# PIC_16F877A_Board.net
KiCad netlist of a schematic drawn in EAGLE
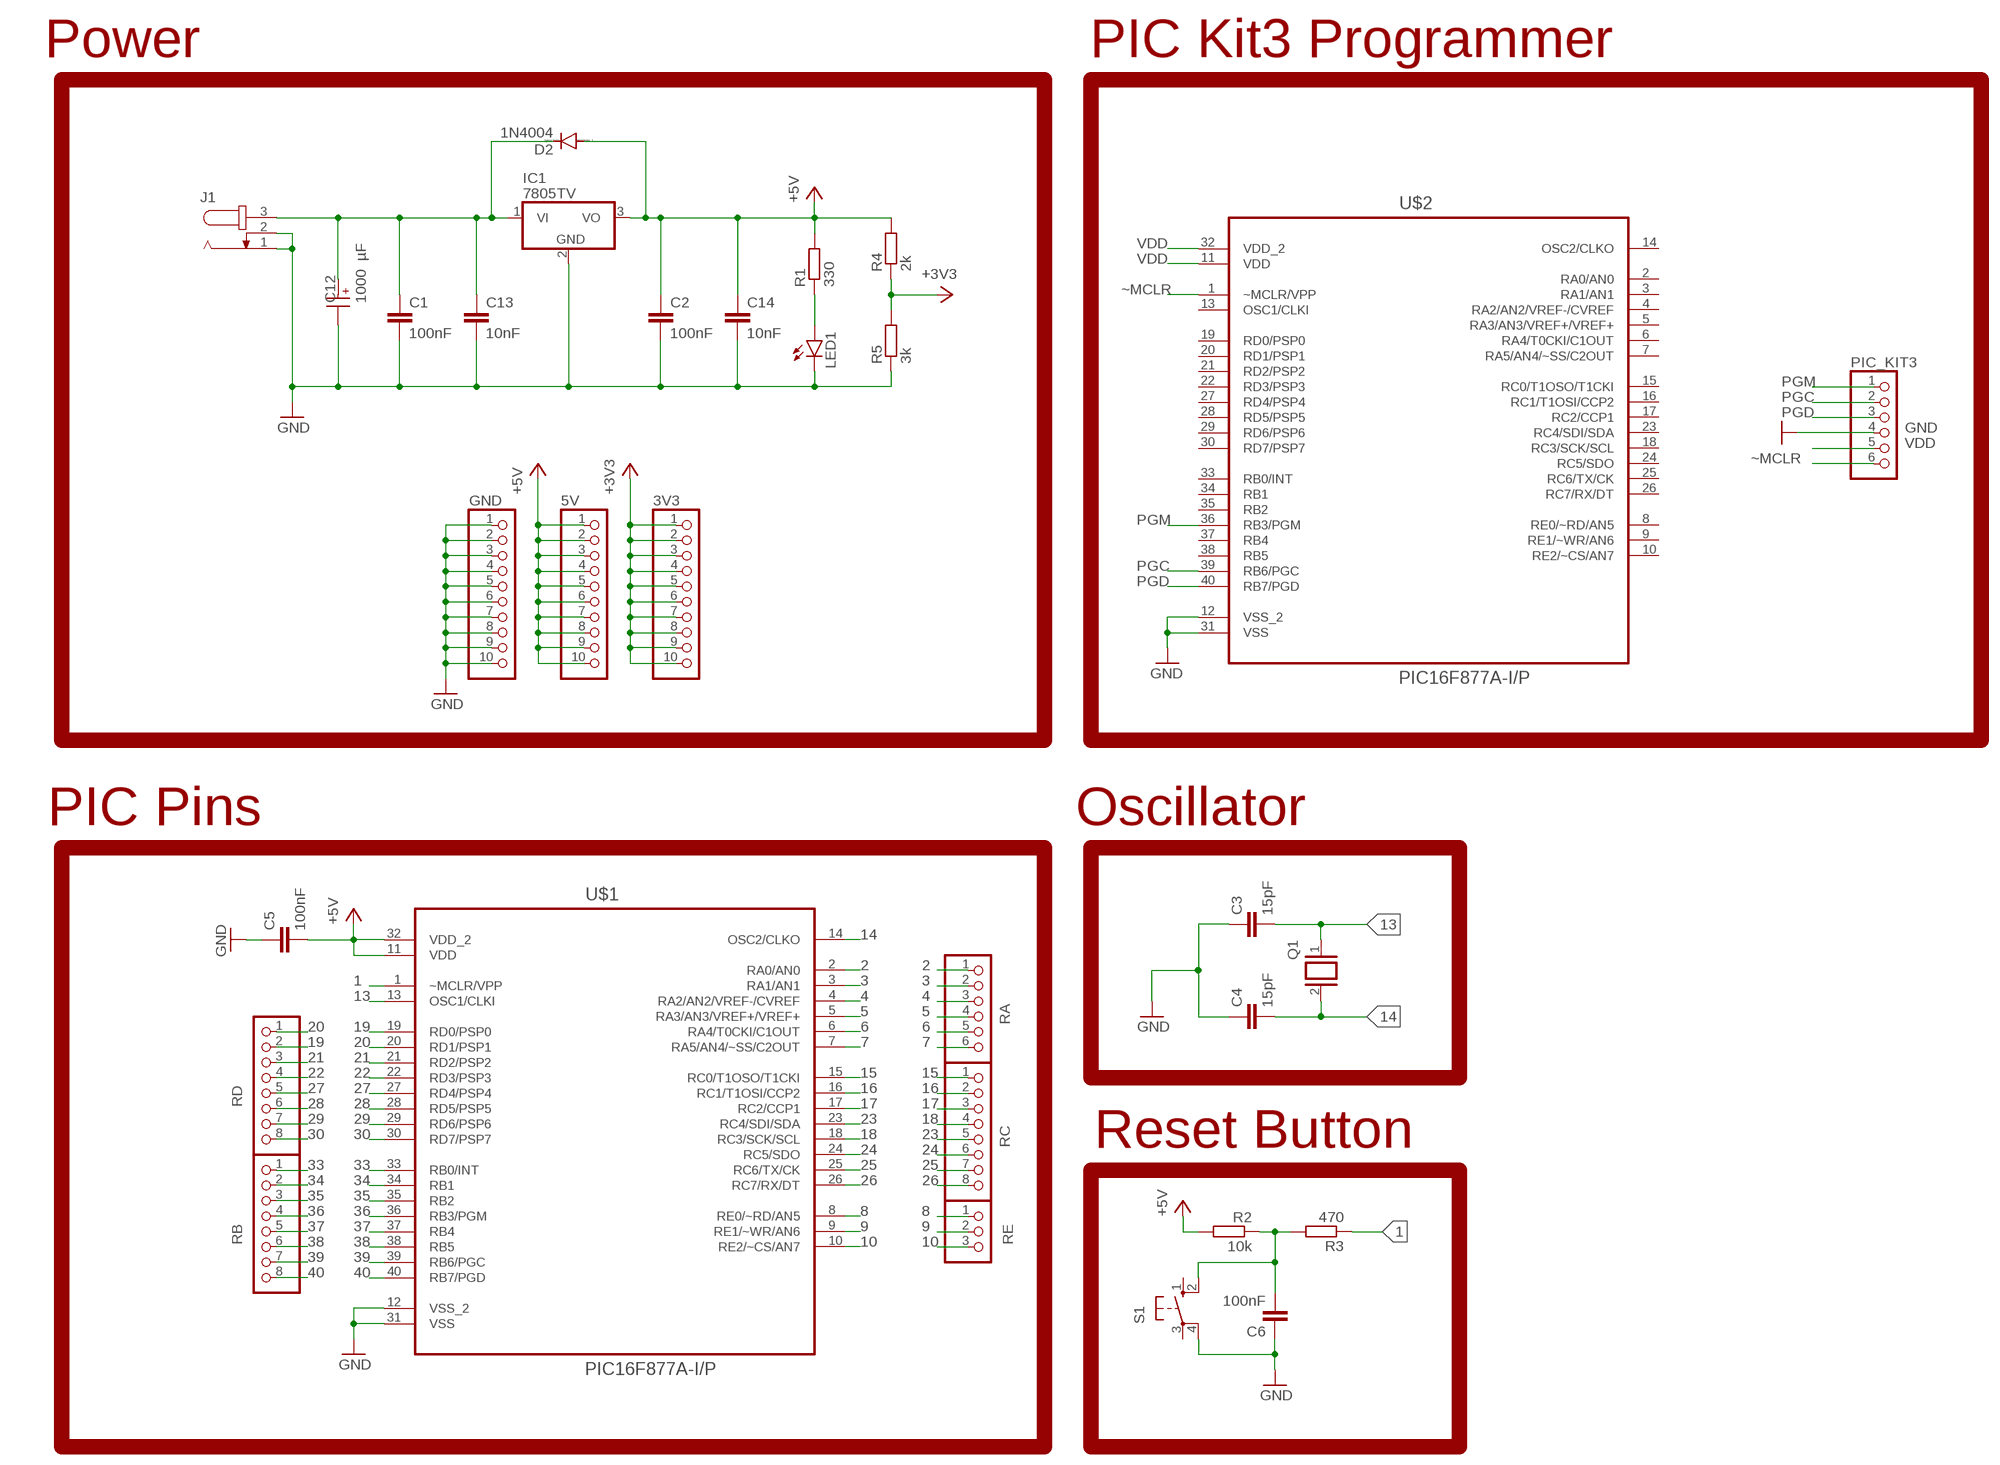
[diagram p0: schematic, sheet 1]

(export (version "E")
  (design (tool "Eeschema 10.0.6"))
  (components
    (comp (ref "3V3")
      (value "PINHD-1X10")
      (footprint "eagle-import:1X10")
      (libsource (lib "eagle-import") (part "PINHD-1X10"))
    )
    (comp (ref "5V")
      (value "PINHD-1X10")
      (footprint "eagle-import:1X10")
      (libsource (lib "eagle-import") (part "PINHD-1X10"))
    )
    (comp (ref "C1")
      (value "100nF")
      (footprint "eagle-import:C025-025X050")
      (libsource (lib "eagle-import") (part "C-EU025-025X050"))
    )
    (comp (ref "C2")
      (value "100nF")
      (footprint "eagle-import:C025-025X050")
      (libsource (lib "eagle-import") (part "C-EU025-025X050"))
    )
    (comp (ref "C3")
      (value "15pF")
      (footprint "eagle-import:C025-025X050")
      (libsource (lib "eagle-import") (part "C-EU025-025X050"))
    )
    (comp (ref "C4")
      (value "15pF")
      (footprint "eagle-import:C025-025X050")
      (libsource (lib "eagle-import") (part "C-EU025-025X050"))
    )
    (comp (ref "C5")
      (value "100nF")
      (footprint "eagle-import:C025-025X050")
      (libsource (lib "eagle-import") (part "C-EU025-025X050"))
    )
    (comp (ref "C6")
      (value "100nF")
      (footprint "eagle-import:C025-025X050")
      (libsource (lib "eagle-import") (part "C-EU025-025X050"))
    )
    (comp (ref "C12")
      (value "1000 µF")
      (footprint "eagle-import:WCAP-ATG8_10X12.5(DXL)")
      (libsource (lib "eagle-import") (part "WCAP-ATG8_10X12.5_860010275016"))
    )
    (comp (ref "C13")
      (value "10nF")
      (footprint "eagle-import:C025-025X050")
      (libsource (lib "eagle-import") (part "C-EU025-025X050"))
    )
    (comp (ref "C14")
      (value "10nF")
      (footprint "eagle-import:C025-025X050")
      (libsource (lib "eagle-import") (part "C-EU025-025X050"))
    )
    (comp (ref "D2")
      (value "1N4004")
      (footprint "eagle-import:DO41-10")
      (libsource (lib "eagle-import") (part "1N4004"))
    )
    (comp (ref "GND")
      (value "PINHD-1X10")
      (footprint "eagle-import:1X10")
      (libsource (lib "eagle-import") (part "PINHD-1X10"))
    )
    (comp (ref "IC1")
      (value "7805TV")
      (footprint "eagle-import:TO220V")
      (libsource (lib "eagle-import") (part "78TV05"))
    )
    (comp (ref "J1")
      (value "JACK-PLUG0")
      (footprint "eagle-import:SPC4077")
      (libsource (lib "eagle-import") (part "JACK-PLUG0"))
    )
    (comp (ref "LED1")
      (value "LED3MM")
      (footprint "eagle-import:LED3MM")
      (libsource (lib "eagle-import") (part "LED3MM"))
    )
    (comp (ref "PIC_KIT3")
      (value "PINHD-1X6")
      (footprint "eagle-import:1X06")
      (libsource (lib "eagle-import") (part "PINHD-1X6"))
    )
    (comp (ref "Q1")
      (value "XTAL/S")
      (footprint "eagle-import:QS")
      (libsource (lib "eagle-import") (part "XTAL/S"))
    )
    (comp (ref "R1")
      (value "330")
      (footprint "eagle-import:0204_7")
      (libsource (lib "eagle-import") (part "R-EU_0204/7"))
    )
    (comp (ref "R2")
      (value "10k")
      (footprint "eagle-import:0204_7")
      (libsource (lib "eagle-import") (part "R-EU_0204/7"))
    )
    (comp (ref "R3")
      (value "470")
      (footprint "eagle-import:0204_7")
      (libsource (lib "eagle-import") (part "R-EU_0204/7"))
    )
    (comp (ref "R4")
      (value "2k")
      (footprint "eagle-import:0204_7")
      (libsource (lib "eagle-import") (part "R-EU_0204/7"))
    )
    (comp (ref "R5")
      (value "3k")
      (footprint "eagle-import:0204_7")
      (libsource (lib "eagle-import") (part "R-EU_0204/7"))
    )
    (comp (ref "RA")
      (value "PINHD-1X6")
      (footprint "eagle-import:1X06")
      (libsource (lib "eagle-import") (part "PINHD-1X6"))
    )
    (comp (ref "RB")
      (value "PINHD-1X8")
      (footprint "eagle-import:1X08")
      (libsource (lib "eagle-import") (part "PINHD-1X8"))
    )
    (comp (ref "RC")
      (value "PINHD-1X8")
      (footprint "eagle-import:1X08")
      (libsource (lib "eagle-import") (part "PINHD-1X8"))
    )
    (comp (ref "RD")
      (value "PINHD-1X8")
      (footprint "eagle-import:1X08")
      (libsource (lib "eagle-import") (part "PINHD-1X8"))
    )
    (comp (ref "RE")
      (value "PINHD-1X3")
      (footprint "eagle-import:1X03")
      (libsource (lib "eagle-import") (part "PINHD-1X3"))
    )
    (comp (ref "S1")
      (value "10-XX")
      (footprint "eagle-import:B3F-10XX")
      (fields (field (name "MPN") "B3F-1000"))
      (libsource (lib "eagle-import") (part "10-XX"))
    )
    (comp (ref "U$1")
      (value "PIC16F877A-I/P")
      (footprint "eagle-import:16F877A")
      (fields (field (name "MF") "Microchip"))
      (libsource (lib "eagle-import") (part "PIC16F877A-I/P"))
    )
    (comp (ref "U$2")
      (value "PIC16F877A-I/P")
      (footprint "eagle-import:16F877A")
      (fields (field (name "MF") "Microchip"))
      (libsource (lib "eagle-import") (part "PIC16F877A-I/P"))
    )
  )
  (nets
    (net (code "1") (name "+3V3") (class "Default")
      (node (ref "3V3") (pin "1") (pinfunction "1_1") (pintype "passive"))
      (node (ref "3V3") (pin "10") (pinfunction "10_10") (pintype "passive"))
      (node (ref "3V3") (pin "2") (pinfunction "2_2") (pintype "passive"))
      (node (ref "3V3") (pin "3") (pinfunction "3_3") (pintype "passive"))
      (node (ref "3V3") (pin "4") (pinfunction "4_4") (pintype "passive"))
      (node (ref "3V3") (pin "5") (pinfunction "5_5") (pintype "passive"))
      (node (ref "3V3") (pin "6") (pinfunction "6_6") (pintype "passive"))
      (node (ref "3V3") (pin "7") (pinfunction "7_7") (pintype "passive"))
      (node (ref "3V3") (pin "8") (pinfunction "8_8") (pintype "passive"))
      (node (ref "3V3") (pin "9") (pinfunction "9_9") (pintype "passive"))
      (node (ref "R4") (pin "1") (pinfunction "1_1") (pintype "passive"))
      (node (ref "R5") (pin "2") (pinfunction "2_2") (pintype "passive"))
    )
    (net (code "2") (name "+5V") (class "Default")
      (node (ref "5V") (pin "1") (pinfunction "1_1") (pintype "passive"))
      (node (ref "5V") (pin "10") (pinfunction "10_10") (pintype "passive"))
      (node (ref "5V") (pin "2") (pinfunction "2_2") (pintype "passive"))
      (node (ref "5V") (pin "3") (pinfunction "3_3") (pintype "passive"))
      (node (ref "5V") (pin "4") (pinfunction "4_4") (pintype "passive"))
      (node (ref "5V") (pin "5") (pinfunction "5_5") (pintype "passive"))
      (node (ref "5V") (pin "6") (pinfunction "6_6") (pintype "passive"))
      (node (ref "5V") (pin "7") (pinfunction "7_7") (pintype "passive"))
      (node (ref "5V") (pin "8") (pinfunction "8_8") (pintype "passive"))
      (node (ref "5V") (pin "9") (pinfunction "9_9") (pintype "passive"))
      (node (ref "C14") (pin "1") (pinfunction "1_1") (pintype "passive"))
      (node (ref "C2") (pin "1") (pinfunction "1_1") (pintype "passive"))
      (node (ref "C5") (pin "2") (pinfunction "2_2") (pintype "passive"))
      (node (ref "D2") (pin "A") (pinfunction "A_A") (pintype "passive"))
      (node (ref "IC1") (pin "3") (pinfunction "VO_3") (pintype "passive"))
      (node (ref "R1") (pin "2") (pinfunction "2_2") (pintype "passive"))
      (node (ref "R2") (pin "2") (pinfunction "2_2") (pintype "passive"))
      (node (ref "R4") (pin "2") (pinfunction "2_2") (pintype "passive"))
      (node (ref "U$1") (pin "11") (pinfunction "VDD_11") (pintype "power_in"))
      (node (ref "U$1") (pin "32") (pinfunction "VDD_2_32") (pintype "power_in"))
    )
    (net (code "3") (name "/2") (class "Default")
      (node (ref "RA") (pin "1") (pinfunction "1_1") (pintype "passive"))
      (node (ref "U$1") (pin "2") (pinfunction "RA0/AN0_2") (pintype "bidirectional"))
    )
    (net (code "4") (name "/3") (class "Default")
      (node (ref "RA") (pin "2") (pinfunction "2_2") (pintype "passive"))
      (node (ref "U$1") (pin "3") (pinfunction "RA1/AN1_3") (pintype "bidirectional"))
    )
    (net (code "5") (name "/4") (class "Default")
      (node (ref "RA") (pin "3") (pinfunction "3_3") (pintype "passive"))
      (node (ref "U$1") (pin "4") (pinfunction "RA2/AN2/VREF-/CVREF_4") (pintype "bidirectional"))
    )
    (net (code "6") (name "/5") (class "Default")
      (node (ref "RA") (pin "4") (pinfunction "4_4") (pintype "passive"))
      (node (ref "U$1") (pin "5") (pinfunction "RA3/AN3/VREF+/VREF+_5") (pintype "bidirectional"))
    )
    (net (code "7") (name "/6") (class "Default")
      (node (ref "RA") (pin "5") (pinfunction "5_5") (pintype "passive"))
      (node (ref "U$1") (pin "6") (pinfunction "RA4/T0CKI/C1OUT_6") (pintype "bidirectional"))
    )
    (net (code "8") (name "/7") (class "Default")
      (node (ref "RA") (pin "6") (pinfunction "6_6") (pintype "passive"))
      (node (ref "U$1") (pin "7") (pinfunction "RA5/AN4/~{SS/C2OUT}_7") (pintype "bidirectional"))
    )
    (net (code "9") (name "/8") (class "Default")
      (node (ref "RE") (pin "1") (pinfunction "1_1") (pintype "passive"))
      (node (ref "U$1") (pin "8") (pinfunction "RE0/~{RD/AN5}_8") (pintype "bidirectional"))
    )
    (net (code "10") (name "/9") (class "Default")
      (node (ref "RE") (pin "2") (pinfunction "2_2") (pintype "passive"))
      (node (ref "U$1") (pin "9") (pinfunction "RE1/~{WR/AN6}_9") (pintype "bidirectional"))
    )
    (net (code "11") (name "/10") (class "Default")
      (node (ref "RE") (pin "3") (pinfunction "3_3") (pintype "passive"))
      (node (ref "U$1") (pin "10") (pinfunction "RE2/~{CS/AN7}_10") (pintype "bidirectional"))
    )
    (net (code "12") (name "/15") (class "Default")
      (node (ref "RC") (pin "1") (pinfunction "1_1") (pintype "passive"))
      (node (ref "U$1") (pin "15") (pinfunction "RC0/T1OSO/T1CKI_15") (pintype "bidirectional"))
    )
    (net (code "13") (name "/16") (class "Default")
      (node (ref "RC") (pin "2") (pinfunction "2_2") (pintype "passive"))
      (node (ref "U$1") (pin "16") (pinfunction "RC1/T1OSI/CCP2_16") (pintype "bidirectional"))
    )
    (net (code "14") (name "/17") (class "Default")
      (node (ref "RC") (pin "3") (pinfunction "3_3") (pintype "passive"))
      (node (ref "U$1") (pin "17") (pinfunction "RC2/CCP1_17") (pintype "bidirectional"))
    )
    (net (code "15") (name "/18") (class "Default")
      (node (ref "RC") (pin "4") (pinfunction "4_4") (pintype "passive"))
      (node (ref "U$1") (pin "18") (pinfunction "RC3/SCK/SCL_18") (pintype "bidirectional"))
    )
    (net (code "16") (name "/19") (class "Default")
      (node (ref "RD") (pin "2") (pinfunction "2_2") (pintype "passive"))
      (node (ref "U$1") (pin "19") (pinfunction "RD0/PSP0_19") (pintype "bidirectional"))
    )
    (net (code "17") (name "/20") (class "Default")
      (node (ref "RD") (pin "1") (pinfunction "1_1") (pintype "passive"))
      (node (ref "U$1") (pin "20") (pinfunction "RD1/PSP1_20") (pintype "bidirectional"))
    )
    (net (code "18") (name "/21") (class "Default")
      (node (ref "RD") (pin "3") (pinfunction "3_3") (pintype "passive"))
      (node (ref "U$1") (pin "21") (pinfunction "RD2/PSP2_21") (pintype "bidirectional"))
    )
    (net (code "19") (name "/22") (class "Default")
      (node (ref "RD") (pin "4") (pinfunction "4_4") (pintype "passive"))
      (node (ref "U$1") (pin "22") (pinfunction "RD3/PSP3_22") (pintype "bidirectional"))
    )
    (net (code "20") (name "/23") (class "Default")
      (node (ref "RC") (pin "5") (pinfunction "5_5") (pintype "passive"))
      (node (ref "U$1") (pin "23") (pinfunction "RC4/SDI/SDA_23") (pintype "bidirectional"))
    )
    (net (code "21") (name "/24") (class "Default")
      (node (ref "RC") (pin "6") (pinfunction "6_6") (pintype "passive"))
      (node (ref "U$1") (pin "24") (pinfunction "RC5/SDO_24") (pintype "bidirectional"))
    )
    (net (code "22") (name "/25") (class "Default")
      (node (ref "RC") (pin "7") (pinfunction "7_7") (pintype "passive"))
      (node (ref "U$1") (pin "25") (pinfunction "RC6/TX/CK_25") (pintype "bidirectional"))
    )
    (net (code "23") (name "/26") (class "Default")
      (node (ref "RC") (pin "8") (pinfunction "8_8") (pintype "passive"))
      (node (ref "U$1") (pin "26") (pinfunction "RC7/RX/DT_26") (pintype "bidirectional"))
    )
    (net (code "24") (name "/27") (class "Default")
      (node (ref "RD") (pin "5") (pinfunction "5_5") (pintype "passive"))
      (node (ref "U$1") (pin "27") (pinfunction "RD4/PSP4_27") (pintype "bidirectional"))
    )
    (net (code "25") (name "/28") (class "Default")
      (node (ref "RD") (pin "6") (pinfunction "6_6") (pintype "passive"))
      (node (ref "U$1") (pin "28") (pinfunction "RD5/PSP5_28") (pintype "bidirectional"))
    )
    (net (code "26") (name "/29") (class "Default")
      (node (ref "RD") (pin "7") (pinfunction "7_7") (pintype "passive"))
      (node (ref "U$1") (pin "29") (pinfunction "RD6/PSP6_29") (pintype "bidirectional"))
    )
    (net (code "27") (name "/30") (class "Default")
      (node (ref "RD") (pin "8") (pinfunction "8_8") (pintype "passive"))
      (node (ref "U$1") (pin "30") (pinfunction "RD7/PSP7_30") (pintype "bidirectional"))
    )
    (net (code "28") (name "/33") (class "Default")
      (node (ref "RB") (pin "1") (pinfunction "1_1") (pintype "passive"))
      (node (ref "U$1") (pin "33") (pinfunction "RB0/INT_33") (pintype "bidirectional"))
    )
    (net (code "29") (name "/34") (class "Default")
      (node (ref "RB") (pin "2") (pinfunction "2_2") (pintype "passive"))
      (node (ref "U$1") (pin "34") (pinfunction "RB1_34") (pintype "bidirectional"))
    )
    (net (code "30") (name "/35") (class "Default")
      (node (ref "RB") (pin "3") (pinfunction "3_3") (pintype "passive"))
      (node (ref "U$1") (pin "35") (pinfunction "RB2_35") (pintype "bidirectional"))
    )
    (net (code "31") (name "/36") (class "Default")
      (node (ref "RB") (pin "4") (pinfunction "4_4") (pintype "passive"))
      (node (ref "U$1") (pin "36") (pinfunction "RB3/PGM_36") (pintype "bidirectional"))
    )
    (net (code "32") (name "/37") (class "Default")
      (node (ref "RB") (pin "5") (pinfunction "5_5") (pintype "passive"))
      (node (ref "U$1") (pin "37") (pinfunction "RB4_37") (pintype "bidirectional"))
    )
    (net (code "33") (name "/38") (class "Default")
      (node (ref "RB") (pin "6") (pinfunction "6_6") (pintype "passive"))
      (node (ref "U$1") (pin "38") (pinfunction "RB5_38") (pintype "bidirectional"))
    )
    (net (code "34") (name "/39") (class "Default")
      (node (ref "RB") (pin "7") (pinfunction "7_7") (pintype "passive"))
      (node (ref "U$1") (pin "39") (pinfunction "RB6/PGC_39") (pintype "bidirectional"))
    )
    (net (code "35") (name "/40") (class "Default")
      (node (ref "RB") (pin "8") (pinfunction "8_8") (pintype "passive"))
      (node (ref "U$1") (pin "40") (pinfunction "RB7/PGD_40") (pintype "bidirectional"))
    )
    (net (code "36") (name "/PGC") (class "Default")
      (node (ref "PIC_KIT3") (pin "2") (pinfunction "2_2") (pintype "passive"))
      (node (ref "U$2") (pin "39") (pinfunction "RB6/PGC_39") (pintype "bidirectional"))
    )
    (net (code "37") (name "/PGD") (class "Default")
      (node (ref "PIC_KIT3") (pin "3") (pinfunction "3_3") (pintype "passive"))
      (node (ref "U$2") (pin "40") (pinfunction "RB7/PGD_40") (pintype "bidirectional"))
    )
    (net (code "38") (name "/PGM") (class "Default")
      (node (ref "PIC_KIT3") (pin "1") (pinfunction "1_1") (pintype "passive"))
      (node (ref "U$2") (pin "36") (pinfunction "RB3/PGM_36") (pintype "bidirectional"))
    )
    (net (code "39") (name "/VDD") (class "Default")
      (node (ref "PIC_KIT3") (pin "5") (pinfunction "5_5") (pintype "passive"))
      (node (ref "U$2") (pin "11") (pinfunction "VDD_11") (pintype "power_in"))
      (node (ref "U$2") (pin "32") (pinfunction "VDD_2_32") (pintype "power_in"))
    )
    (net (code "40") (name "/~{MCLR}") (class "Default")
      (node (ref "PIC_KIT3") (pin "6") (pinfunction "6_6") (pintype "passive"))
      (node (ref "U$2") (pin "1") (pinfunction "~{MCLR/VPP}_1") (pintype "input"))
    )
    (net (code "41") (name "1") (class "Default")
      (node (ref "R3") (pin "1") (pinfunction "1_1") (pintype "passive"))
      (node (ref "U$1") (pin "1") (pinfunction "~{MCLR/VPP}_1") (pintype "input"))
    )
    (net (code "42") (name "13") (class "Default")
      (node (ref "C3") (pin "2") (pinfunction "2_2") (pintype "passive"))
      (node (ref "Q1") (pin "1") (pinfunction "1_1") (pintype "passive"))
      (node (ref "U$1") (pin "13") (pinfunction "OSC1/CLKI_13") (pintype "input"))
    )
    (net (code "43") (name "14") (class "Default")
      (node (ref "C4") (pin "2") (pinfunction "2_2") (pintype "passive"))
      (node (ref "Q1") (pin "2") (pinfunction "2_2") (pintype "passive"))
      (node (ref "U$1") (pin "14") (pinfunction "OSC2/CLKO_14") (pintype "output"))
    )
    (net (code "44") (name "GND") (class "Default")
      (node (ref "C1") (pin "2") (pinfunction "2_2") (pintype "passive"))
      (node (ref "C12") (pin "2") (pinfunction "-_2") (pintype "passive"))
      (node (ref "C13") (pin "2") (pinfunction "2_2") (pintype "passive"))
      (node (ref "C14") (pin "2") (pinfunction "2_2") (pintype "passive"))
      (node (ref "C2") (pin "2") (pinfunction "2_2") (pintype "passive"))
      (node (ref "C3") (pin "1") (pinfunction "1_1") (pintype "passive"))
      (node (ref "C4") (pin "1") (pinfunction "1_1") (pintype "passive"))
      (node (ref "C5") (pin "1") (pinfunction "1_1") (pintype "passive"))
      (node (ref "C6") (pin "1") (pinfunction "1_1") (pintype "passive"))
      (node (ref "GND") (pin "1") (pinfunction "1_1") (pintype "passive"))
      (node (ref "GND") (pin "10") (pinfunction "10_10") (pintype "passive"))
      (node (ref "GND") (pin "2") (pinfunction "2_2") (pintype "passive"))
      (node (ref "GND") (pin "3") (pinfunction "3_3") (pintype "passive"))
      (node (ref "GND") (pin "4") (pinfunction "4_4") (pintype "passive"))
      (node (ref "GND") (pin "5") (pinfunction "5_5") (pintype "passive"))
      (node (ref "GND") (pin "6") (pinfunction "6_6") (pintype "passive"))
      (node (ref "GND") (pin "7") (pinfunction "7_7") (pintype "passive"))
      (node (ref "GND") (pin "8") (pinfunction "8_8") (pintype "passive"))
      (node (ref "GND") (pin "9") (pinfunction "9_9") (pintype "passive"))
      (node (ref "IC1") (pin "2") (pinfunction "GND_2") (pintype "passive"))
      (node (ref "J1") (pin "1") (pinfunction "1_1") (pintype "passive"))
      (node (ref "J1") (pin "2") (pinfunction "2_2") (pintype "passive"))
      (node (ref "LED1") (pin "K") (pinfunction "C_K") (pintype "passive"))
      (node (ref "PIC_KIT3") (pin "4") (pinfunction "4_4") (pintype "passive"))
      (node (ref "R5") (pin "1") (pinfunction "1_1") (pintype "passive"))
      (node (ref "S1") (pin "4") (pinfunction "P1_4") (pintype "passive"))
      (node (ref "U$1") (pin "12") (pinfunction "VSS_2_12") (pintype "power_in"))
      (node (ref "U$1") (pin "31") (pinfunction "VSS_31") (pintype "power_in"))
      (node (ref "U$2") (pin "12") (pinfunction "VSS_2_12") (pintype "power_in"))
      (node (ref "U$2") (pin "31") (pinfunction "VSS_31") (pintype "power_in"))
    )
    (net (code "45") (name "Net-(C12-+)") (class "Default")
      (node (ref "C1") (pin "1") (pinfunction "1_1") (pintype "passive"))
      (node (ref "C12") (pin "1") (pinfunction "+_1") (pintype "passive"))
      (node (ref "C13") (pin "1") (pinfunction "1_1") (pintype "passive"))
      (node (ref "D2") (pin "C") (pinfunction "C_C") (pintype "passive"))
      (node (ref "IC1") (pin "1") (pinfunction "VI_1") (pintype "input"))
      (node (ref "J1") (pin "3") (pinfunction "3_3") (pintype "passive"))
    )
    (net (code "46") (name "Net-(LED1-PadA)") (class "Default")
      (node (ref "LED1") (pin "A") (pinfunction "A_A") (pintype "passive"))
      (node (ref "R1") (pin "1") (pinfunction "1_1") (pintype "passive"))
    )
    (net (code "47") (name "Net-(S1-S1)") (class "Default")
      (node (ref "C6") (pin "2") (pinfunction "2_2") (pintype "passive"))
      (node (ref "R2") (pin "1") (pinfunction "1_1") (pintype "passive"))
      (node (ref "R3") (pin "2") (pinfunction "2_2") (pintype "passive"))
      (node (ref "S1") (pin "2") (pinfunction "S1_2") (pintype "passive"))
    )
    (net (code "48") (name "unconnected-(S1-P-Pad3)") (class "Default")
      (node (ref "S1") (pin "3") (pinfunction "P_3") (pintype "passive"))
    )
    (net (code "49") (name "unconnected-(S1-S-Pad1)") (class "Default")
      (node (ref "S1") (pin "1") (pinfunction "S_1") (pintype "passive"))
    )
    (net (code "50") (name "unconnected-(U$2-OSC1{slash}CLKI-Pad13)") (class "Default")
      (node (ref "U$2") (pin "13") (pinfunction "OSC1/CLKI_13") (pintype "input"))
    )
    (net (code "51") (name "unconnected-(U$2-OSC2{slash}CLKO-Pad14)") (class "Default")
      (node (ref "U$2") (pin "14") (pinfunction "OSC2/CLKO_14") (pintype "output"))
    )
    (net (code "52") (name "unconnected-(U$2-RA0{slash}AN0-Pad2)") (class "Default")
      (node (ref "U$2") (pin "2") (pinfunction "RA0/AN0_2") (pintype "bidirectional"))
    )
    (net (code "53") (name "unconnected-(U$2-RA1{slash}AN1-Pad3)") (class "Default")
      (node (ref "U$2") (pin "3") (pinfunction "RA1/AN1_3") (pintype "bidirectional"))
    )
    (net (code "54") (name "unconnected-(U$2-RA2{slash}AN2{slash}VREF-{slash}CVREF-Pad4)") (class "Default")
      (node (ref "U$2") (pin "4") (pinfunction "RA2/AN2/VREF-/CVREF_4") (pintype "bidirectional"))
    )
    (net (code "55") (name "unconnected-(U$2-RA3{slash}AN3{slash}VREF+{slash}VREF+-Pad5)") (class "Default")
      (node (ref "U$2") (pin "5") (pinfunction "RA3/AN3/VREF+/VREF+_5") (pintype "bidirectional"))
    )
    (net (code "56") (name "unconnected-(U$2-RA4{slash}T0CKI{slash}C1OUT-Pad6)") (class "Default")
      (node (ref "U$2") (pin "6") (pinfunction "RA4/T0CKI/C1OUT_6") (pintype "bidirectional"))
    )
    (net (code "57") (name "unconnected-(U$2-RA5{slash}AN4{slash}~{SS{slash}C2OUT}-Pad7)") (class "Default")
      (node (ref "U$2") (pin "7") (pinfunction "RA5/AN4/~{SS/C2OUT}_7") (pintype "bidirectional"))
    )
    (net (code "58") (name "unconnected-(U$2-RB0{slash}INT-Pad33)") (class "Default")
      (node (ref "U$2") (pin "33") (pinfunction "RB0/INT_33") (pintype "bidirectional"))
    )
    (net (code "59") (name "unconnected-(U$2-RB1-Pad34)") (class "Default")
      (node (ref "U$2") (pin "34") (pinfunction "RB1_34") (pintype "bidirectional"))
    )
    (net (code "60") (name "unconnected-(U$2-RB2-Pad35)") (class "Default")
      (node (ref "U$2") (pin "35") (pinfunction "RB2_35") (pintype "bidirectional"))
    )
    (net (code "61") (name "unconnected-(U$2-RB4-Pad37)") (class "Default")
      (node (ref "U$2") (pin "37") (pinfunction "RB4_37") (pintype "bidirectional"))
    )
    (net (code "62") (name "unconnected-(U$2-RB5-Pad38)") (class "Default")
      (node (ref "U$2") (pin "38") (pinfunction "RB5_38") (pintype "bidirectional"))
    )
    (net (code "63") (name "unconnected-(U$2-RC0{slash}T1OSO{slash}T1CKI-Pad15)") (class "Default")
      (node (ref "U$2") (pin "15") (pinfunction "RC0/T1OSO/T1CKI_15") (pintype "bidirectional"))
    )
    (net (code "64") (name "unconnected-(U$2-RC1{slash}T1OSI{slash}CCP2-Pad16)") (class "Default")
      (node (ref "U$2") (pin "16") (pinfunction "RC1/T1OSI/CCP2_16") (pintype "bidirectional"))
    )
    (net (code "65") (name "unconnected-(U$2-RC2{slash}CCP1-Pad17)") (class "Default")
      (node (ref "U$2") (pin "17") (pinfunction "RC2/CCP1_17") (pintype "bidirectional"))
    )
    (net (code "66") (name "unconnected-(U$2-RC3{slash}SCK{slash}SCL-Pad18)") (class "Default")
      (node (ref "U$2") (pin "18") (pinfunction "RC3/SCK/SCL_18") (pintype "bidirectional"))
    )
    (net (code "67") (name "unconnected-(U$2-RC4{slash}SDI{slash}SDA-Pad23)") (class "Default")
      (node (ref "U$2") (pin "23") (pinfunction "RC4/SDI/SDA_23") (pintype "bidirectional"))
    )
    (net (code "68") (name "unconnected-(U$2-RC5{slash}SDO-Pad24)") (class "Default")
      (node (ref "U$2") (pin "24") (pinfunction "RC5/SDO_24") (pintype "bidirectional"))
    )
    (net (code "69") (name "unconnected-(U$2-RC6{slash}TX{slash}CK-Pad25)") (class "Default")
      (node (ref "U$2") (pin "25") (pinfunction "RC6/TX/CK_25") (pintype "bidirectional"))
    )
    (net (code "70") (name "unconnected-(U$2-RC7{slash}RX{slash}DT-Pad26)") (class "Default")
      (node (ref "U$2") (pin "26") (pinfunction "RC7/RX/DT_26") (pintype "bidirectional"))
    )
    (net (code "71") (name "unconnected-(U$2-RD0{slash}PSP0-Pad19)") (class "Default")
      (node (ref "U$2") (pin "19") (pinfunction "RD0/PSP0_19") (pintype "bidirectional"))
    )
    (net (code "72") (name "unconnected-(U$2-RD1{slash}PSP1-Pad20)") (class "Default")
      (node (ref "U$2") (pin "20") (pinfunction "RD1/PSP1_20") (pintype "bidirectional"))
    )
    (net (code "73") (name "unconnected-(U$2-RD2{slash}PSP2-Pad21)") (class "Default")
      (node (ref "U$2") (pin "21") (pinfunction "RD2/PSP2_21") (pintype "bidirectional"))
    )
    (net (code "74") (name "unconnected-(U$2-RD3{slash}PSP3-Pad22)") (class "Default")
      (node (ref "U$2") (pin "22") (pinfunction "RD3/PSP3_22") (pintype "bidirectional"))
    )
    (net (code "75") (name "unconnected-(U$2-RD4{slash}PSP4-Pad27)") (class "Default")
      (node (ref "U$2") (pin "27") (pinfunction "RD4/PSP4_27") (pintype "bidirectional"))
    )
    (net (code "76") (name "unconnected-(U$2-RD5{slash}PSP5-Pad28)") (class "Default")
      (node (ref "U$2") (pin "28") (pinfunction "RD5/PSP5_28") (pintype "bidirectional"))
    )
    (net (code "77") (name "unconnected-(U$2-RD6{slash}PSP6-Pad29)") (class "Default")
      (node (ref "U$2") (pin "29") (pinfunction "RD6/PSP6_29") (pintype "bidirectional"))
    )
    (net (code "78") (name "unconnected-(U$2-RD7{slash}PSP7-Pad30)") (class "Default")
      (node (ref "U$2") (pin "30") (pinfunction "RD7/PSP7_30") (pintype "bidirectional"))
    )
    (net (code "79") (name "unconnected-(U$2-RE0{slash}~{RD{slash}AN5}-Pad8)") (class "Default")
      (node (ref "U$2") (pin "8") (pinfunction "RE0/~{RD/AN5}_8") (pintype "bidirectional"))
    )
    (net (code "80") (name "unconnected-(U$2-RE1{slash}~{WR{slash}AN6}-Pad9)") (class "Default")
      (node (ref "U$2") (pin "9") (pinfunction "RE1/~{WR/AN6}_9") (pintype "bidirectional"))
    )
    (net (code "81") (name "unconnected-(U$2-RE2{slash}~{CS{slash}AN7}-Pad10)") (class "Default")
      (node (ref "U$2") (pin "10") (pinfunction "RE2/~{CS/AN7}_10") (pintype "bidirectional"))
    )
  )
)
